# robo_mantis.net
KiCad netlist of a schematic drawn in EAGLE
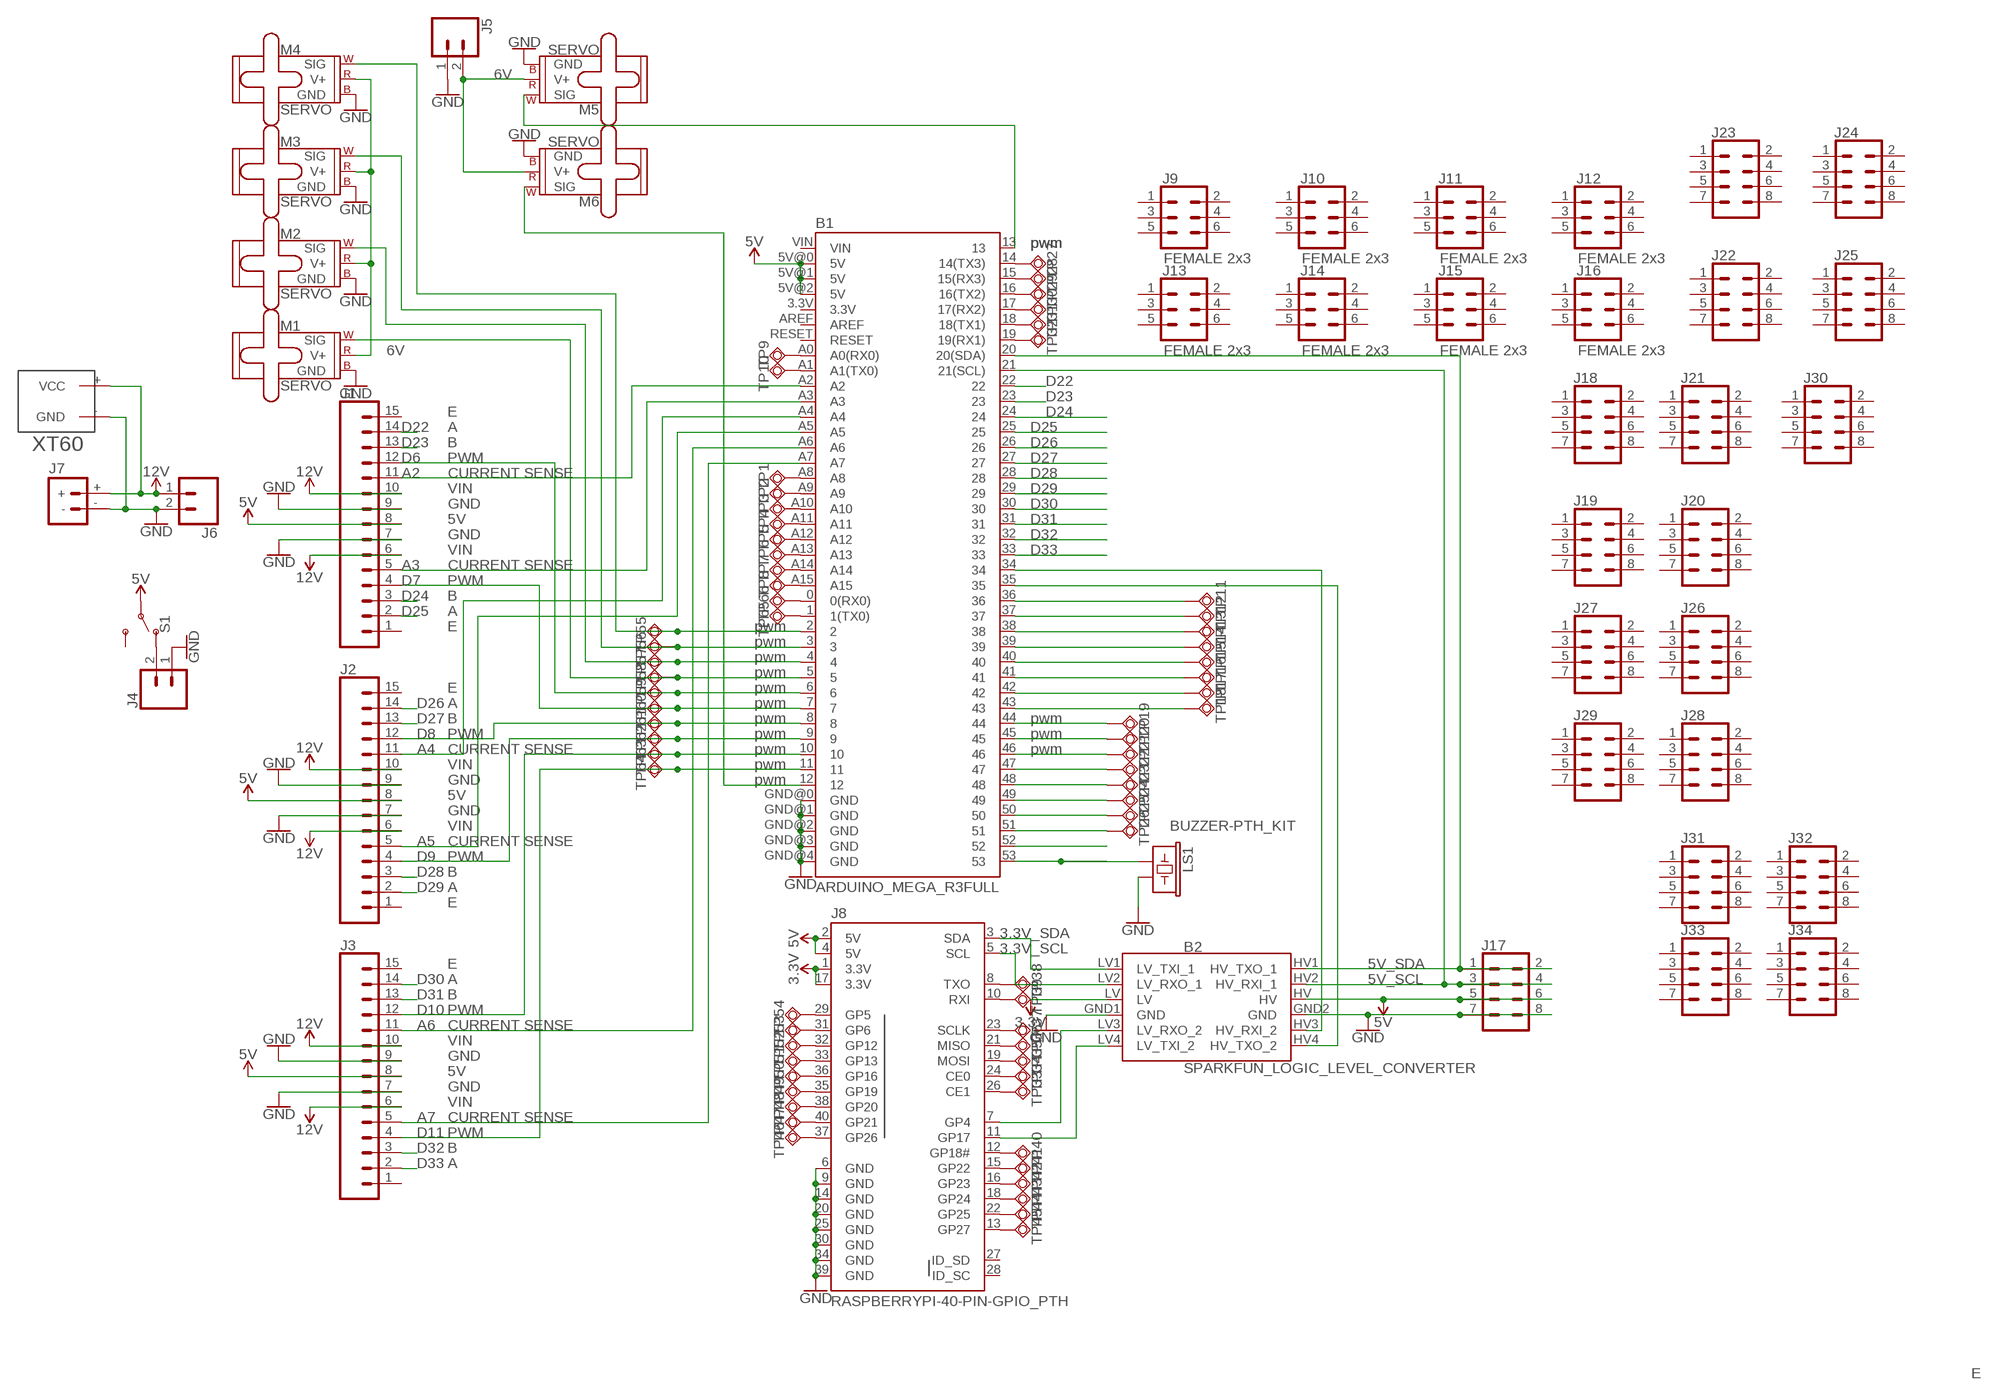
[diagram p0: schematic, sheet 1]

(export (version "E")
  (design (tool "Eeschema 10.0.6"))
  (components
    (comp (ref "B1")
      (value "ARDUINO_MEGA_R3FULL")
      (footprint "eagle-import:ARDUINO_MEGA")
      (libsource (lib "eagle-import") (part "ARDUINO_MEGA_R3FULL"))
    )
    (comp (ref "B2")
      (value "SPARKFUN_LOGIC_LEVEL_CONVERTER")
      (footprint "eagle-import:SPARKFUN_LOGIC_LEVEL_CONVERTER")
      (libsource (lib "eagle-import") (part "SPARKFUN_LOGIC_LEVEL_CONVERTER"))
    )
    (comp (ref "J1")
      (value "CONN_15LOCK_LONGPADS")
      (footprint "eagle-import:1X15_LOCK_LONGPADS")
      (libsource (lib "eagle-import") (part "CONN_15LOCK_LONGPADS"))
    )
    (comp (ref "J2")
      (value "CONN_15LOCK_LONGPADS")
      (footprint "eagle-import:1X15_LOCK_LONGPADS")
      (libsource (lib "eagle-import") (part "CONN_15LOCK_LONGPADS"))
    )
    (comp (ref "J3")
      (value "CONN_15LOCK_LONGPADS")
      (footprint "eagle-import:1X15_LOCK_LONGPADS")
      (libsource (lib "eagle-import") (part "CONN_15LOCK_LONGPADS"))
    )
    (comp (ref "J4")
      (value "CONN_02")
      (footprint "eagle-import:1X02")
      (libsource (lib "eagle-import") (part "CONN_02"))
    )
    (comp (ref "J5")
      (value "CONN_02")
      (footprint "eagle-import:1X02")
      (libsource (lib "eagle-import") (part "CONN_02"))
    )
    (comp (ref "J6")
      (value "CONN_02")
      (footprint "eagle-import:1X02")
      (libsource (lib "eagle-import") (part "CONN_02"))
    )
    (comp (ref "J7")
      (value "BATTERY_CONN_DEANS")
      (footprint "eagle-import:DEANS")
      (libsource (lib "eagle-import") (part "BATTERY_CONN_DEANS"))
    )
    (comp (ref "J8")
      (value "RASPBERRYPI-40-PIN-GPIO_PTH")
      (footprint "eagle-import:2X20_SHROUDED")
      (libsource (lib "eagle-import") (part "RASPBERRYPI-40-PIN-GPIO_PTH"))
    )
    (comp (ref "J9")
      (value "FEMALE 2x3")
      (footprint "eagle-import:2X3")
      (libsource (lib "eagle-import") (part "CONN_03X2FEMALE"))
    )
    (comp (ref "J10")
      (value "FEMALE 2x3")
      (footprint "eagle-import:2X3")
      (libsource (lib "eagle-import") (part "CONN_03X2FEMALE"))
    )
    (comp (ref "J11")
      (value "FEMALE 2x3")
      (footprint "eagle-import:2X3")
      (libsource (lib "eagle-import") (part "CONN_03X2FEMALE"))
    )
    (comp (ref "J12")
      (value "FEMALE 2x3")
      (footprint "eagle-import:2X3")
      (libsource (lib "eagle-import") (part "CONN_03X2FEMALE"))
    )
    (comp (ref "J13")
      (value "FEMALE 2x3")
      (footprint "eagle-import:2X3")
      (libsource (lib "eagle-import") (part "CONN_03X2FEMALE"))
    )
    (comp (ref "J14")
      (value "FEMALE 2x3")
      (footprint "eagle-import:2X3")
      (libsource (lib "eagle-import") (part "CONN_03X2FEMALE"))
    )
    (comp (ref "J15")
      (value "FEMALE 2x3")
      (footprint "eagle-import:2X3")
      (libsource (lib "eagle-import") (part "CONN_03X2FEMALE"))
    )
    (comp (ref "J16")
      (value "FEMALE 2x3")
      (footprint "eagle-import:2X3")
      (libsource (lib "eagle-import") (part "CONN_03X2FEMALE"))
    )
    (comp (ref "J17")
      (value "CONN_04X2")
      (footprint "eagle-import:2X4")
      (libsource (lib "eagle-import") (part "CONN_04X2"))
    )
    (comp (ref "J18")
      (value "CONN_04X2")
      (footprint "eagle-import:2X4")
      (libsource (lib "eagle-import") (part "CONN_04X2"))
    )
    (comp (ref "J19")
      (value "CONN_04X2")
      (footprint "eagle-import:2X4")
      (libsource (lib "eagle-import") (part "CONN_04X2"))
    )
    (comp (ref "J20")
      (value "CONN_04X2")
      (footprint "eagle-import:2X4")
      (libsource (lib "eagle-import") (part "CONN_04X2"))
    )
    (comp (ref "J21")
      (value "CONN_04X2")
      (footprint "eagle-import:2X4")
      (libsource (lib "eagle-import") (part "CONN_04X2"))
    )
    (comp (ref "J22")
      (value "CONN_04X2")
      (footprint "eagle-import:2X4")
      (libsource (lib "eagle-import") (part "CONN_04X2"))
    )
    (comp (ref "J23")
      (value "CONN_04X2")
      (footprint "eagle-import:2X4")
      (libsource (lib "eagle-import") (part "CONN_04X2"))
    )
    (comp (ref "J24")
      (value "CONN_04X2")
      (footprint "eagle-import:2X4")
      (libsource (lib "eagle-import") (part "CONN_04X2"))
    )
    (comp (ref "J25")
      (value "CONN_04X2")
      (footprint "eagle-import:2X4")
      (libsource (lib "eagle-import") (part "CONN_04X2"))
    )
    (comp (ref "J26")
      (value "CONN_04X2")
      (footprint "eagle-import:2X4")
      (libsource (lib "eagle-import") (part "CONN_04X2"))
    )
    (comp (ref "J27")
      (value "CONN_04X2")
      (footprint "eagle-import:2X4")
      (libsource (lib "eagle-import") (part "CONN_04X2"))
    )
    (comp (ref "J28")
      (value "CONN_04X2")
      (footprint "eagle-import:2X4")
      (libsource (lib "eagle-import") (part "CONN_04X2"))
    )
    (comp (ref "J29")
      (value "CONN_04X2")
      (footprint "eagle-import:2X4")
      (libsource (lib "eagle-import") (part "CONN_04X2"))
    )
    (comp (ref "J30")
      (value "CONN_04X2")
      (footprint "eagle-import:2X4")
      (libsource (lib "eagle-import") (part "CONN_04X2"))
    )
    (comp (ref "J31")
      (value "CONN_04X2")
      (footprint "eagle-import:2X4")
      (libsource (lib "eagle-import") (part "CONN_04X2"))
    )
    (comp (ref "J32")
      (value "CONN_04X2")
      (footprint "eagle-import:2X4")
      (libsource (lib "eagle-import") (part "CONN_04X2"))
    )
    (comp (ref "J33")
      (value "CONN_04X2")
      (footprint "eagle-import:2X4")
      (libsource (lib "eagle-import") (part "CONN_04X2"))
    )
    (comp (ref "J34")
      (value "CONN_04X2")
      (footprint "eagle-import:2X4")
      (libsource (lib "eagle-import") (part "CONN_04X2"))
    )
    (comp (ref "LS1")
      (value "BUZZER-PTH_KIT")
      (footprint "eagle-import:BUZZER-12MM-KIT")
      (libsource (lib "eagle-import") (part "BUZZER-PTH_KIT"))
    )
    (comp (ref "M1")
      (value "SERVO")
      (footprint "eagle-import:1X03")
      (libsource (lib "eagle-import") (part "SERVO"))
    )
    (comp (ref "M2")
      (value "SERVO")
      (footprint "eagle-import:1X03")
      (libsource (lib "eagle-import") (part "SERVO"))
    )
    (comp (ref "M3")
      (value "SERVO")
      (footprint "eagle-import:1X03")
      (libsource (lib "eagle-import") (part "SERVO"))
    )
    (comp (ref "M4")
      (value "SERVO")
      (footprint "eagle-import:1X03")
      (libsource (lib "eagle-import") (part "SERVO"))
    )
    (comp (ref "M5")
      (value "SERVO")
      (footprint "eagle-import:1X03")
      (libsource (lib "eagle-import") (part "SERVO"))
    )
    (comp (ref "M6")
      (value "SERVO")
      (footprint "eagle-import:1X03")
      (libsource (lib "eagle-import") (part "SERVO"))
    )
    (comp (ref "S1")
      (value "SWITCH-SPDT-PTH-11.6X4.0MM-LOCK")
      (footprint "eagle-import:SWITCH_SPDT_PTH_11.6X4.0MM_LOCK")
      (libsource (lib "eagle-import") (part "SWITCH-SPDT-PTH-11.6X4.0MM-LOCK"))
    )
    (comp (ref "TP1")
      (value "TESTPAD_TPSQB1,27")
      (footprint "eagle-import:TESTPAD_B1,27")
      (libsource (lib "eagle-import") (part "TESTPAD_TPSQB1,27"))
    )
    (comp (ref "TP2")
      (value "TESTPAD_TPSQB1,27")
      (footprint "eagle-import:TESTPAD_B1,27")
      (libsource (lib "eagle-import") (part "TESTPAD_TPSQB1,27"))
    )
    (comp (ref "TP3")
      (value "TESTPAD_TPSQB1,27")
      (footprint "eagle-import:TESTPAD_B1,27")
      (libsource (lib "eagle-import") (part "TESTPAD_TPSQB1,27"))
    )
    (comp (ref "TP4")
      (value "TESTPAD_TPSQB1,27")
      (footprint "eagle-import:TESTPAD_B1,27")
      (libsource (lib "eagle-import") (part "TESTPAD_TPSQB1,27"))
    )
    (comp (ref "TP5")
      (value "TESTPAD_TPSQB1,27")
      (footprint "eagle-import:TESTPAD_B1,27")
      (libsource (lib "eagle-import") (part "TESTPAD_TPSQB1,27"))
    )
    (comp (ref "TP6")
      (value "TESTPAD_TPSQB1,27")
      (footprint "eagle-import:TESTPAD_B1,27")
      (libsource (lib "eagle-import") (part "TESTPAD_TPSQB1,27"))
    )
    (comp (ref "TP7")
      (value "TESTPAD_TPSQB1,27")
      (footprint "eagle-import:TESTPAD_B1,27")
      (libsource (lib "eagle-import") (part "TESTPAD_TPSQB1,27"))
    )
    (comp (ref "TP8")
      (value "TESTPAD_TPSQB1,27")
      (footprint "eagle-import:TESTPAD_B1,27")
      (libsource (lib "eagle-import") (part "TESTPAD_TPSQB1,27"))
    )
    (comp (ref "TP9")
      (value "TESTPAD_TPSQB1,27")
      (footprint "eagle-import:TESTPAD_B1,27")
      (libsource (lib "eagle-import") (part "TESTPAD_TPSQB1,27"))
    )
    (comp (ref "TP10")
      (value "TESTPAD_TPSQB1,27")
      (footprint "eagle-import:TESTPAD_B1,27")
      (libsource (lib "eagle-import") (part "TESTPAD_TPSQB1,27"))
    )
    (comp (ref "TP11")
      (value "TESTPAD_TPSQB1,27")
      (footprint "eagle-import:TESTPAD_B1,27")
      (libsource (lib "eagle-import") (part "TESTPAD_TPSQB1,27"))
    )
    (comp (ref "TP12")
      (value "TESTPAD_TPSQB1,27")
      (footprint "eagle-import:TESTPAD_B1,27")
      (libsource (lib "eagle-import") (part "TESTPAD_TPSQB1,27"))
    )
    (comp (ref "TP13")
      (value "TESTPAD_TPSQB1,27")
      (footprint "eagle-import:TESTPAD_B1,27")
      (libsource (lib "eagle-import") (part "TESTPAD_TPSQB1,27"))
    )
    (comp (ref "TP14")
      (value "TESTPAD_TPSQB1,27")
      (footprint "eagle-import:TESTPAD_B1,27")
      (libsource (lib "eagle-import") (part "TESTPAD_TPSQB1,27"))
    )
    (comp (ref "TP15")
      (value "TESTPAD_TPSQB1,27")
      (footprint "eagle-import:TESTPAD_B1,27")
      (libsource (lib "eagle-import") (part "TESTPAD_TPSQB1,27"))
    )
    (comp (ref "TP16")
      (value "TESTPAD_TPSQB1,27")
      (footprint "eagle-import:TESTPAD_B1,27")
      (libsource (lib "eagle-import") (part "TESTPAD_TPSQB1,27"))
    )
    (comp (ref "TP17")
      (value "TESTPAD_TPSQB1,27")
      (footprint "eagle-import:TESTPAD_B1,27")
      (libsource (lib "eagle-import") (part "TESTPAD_TPSQB1,27"))
    )
    (comp (ref "TP18")
      (value "TESTPAD_TPSQB1,27")
      (footprint "eagle-import:TESTPAD_B1,27")
      (libsource (lib "eagle-import") (part "TESTPAD_TPSQB1,27"))
    )
    (comp (ref "TP19")
      (value "TESTPAD_TPSQB1,27")
      (footprint "eagle-import:TESTPAD_B1,27")
      (libsource (lib "eagle-import") (part "TESTPAD_TPSQB1,27"))
    )
    (comp (ref "TP20")
      (value "TESTPAD_TPSQB1,27")
      (footprint "eagle-import:TESTPAD_B1,27")
      (libsource (lib "eagle-import") (part "TESTPAD_TPSQB1,27"))
    )
    (comp (ref "TP21")
      (value "TESTPAD_TPSQB1,27")
      (footprint "eagle-import:TESTPAD_B1,27")
      (libsource (lib "eagle-import") (part "TESTPAD_TPSQB1,27"))
    )
    (comp (ref "TP22")
      (value "TESTPAD_TPSQB1,27")
      (footprint "eagle-import:TESTPAD_B1,27")
      (libsource (lib "eagle-import") (part "TESTPAD_TPSQB1,27"))
    )
    (comp (ref "TP23")
      (value "TESTPAD_TPSQB1,27")
      (footprint "eagle-import:TESTPAD_B1,27")
      (libsource (lib "eagle-import") (part "TESTPAD_TPSQB1,27"))
    )
    (comp (ref "TP24")
      (value "TESTPAD_TPSQB1,27")
      (footprint "eagle-import:TESTPAD_B1,27")
      (libsource (lib "eagle-import") (part "TESTPAD_TPSQB1,27"))
    )
    (comp (ref "TP25")
      (value "TESTPAD_TPSQB1,27")
      (footprint "eagle-import:TESTPAD_B1,27")
      (libsource (lib "eagle-import") (part "TESTPAD_TPSQB1,27"))
    )
    (comp (ref "TP26")
      (value "TESTPAD_TPSQB1,27")
      (footprint "eagle-import:TESTPAD_B1,27")
      (libsource (lib "eagle-import") (part "TESTPAD_TPSQB1,27"))
    )
    (comp (ref "TP27")
      (value "TESTPAD_TPSQB1,27")
      (footprint "eagle-import:TESTPAD_B1,27")
      (libsource (lib "eagle-import") (part "TESTPAD_TPSQB1,27"))
    )
    (comp (ref "TP28")
      (value "TESTPAD_TPSQB1,27")
      (footprint "eagle-import:TESTPAD_B1,27")
      (libsource (lib "eagle-import") (part "TESTPAD_TPSQB1,27"))
    )
    (comp (ref "TP29")
      (value "TESTPAD_TPSQB1,27")
      (footprint "eagle-import:TESTPAD_B1,27")
      (libsource (lib "eagle-import") (part "TESTPAD_TPSQB1,27"))
    )
    (comp (ref "TP30")
      (value "TESTPAD_TPSQB1,27")
      (footprint "eagle-import:TESTPAD_B1,27")
      (libsource (lib "eagle-import") (part "TESTPAD_TPSQB1,27"))
    )
    (comp (ref "TP31")
      (value "TESTPAD_TPSQB1,27")
      (footprint "eagle-import:TESTPAD_B1,27")
      (libsource (lib "eagle-import") (part "TESTPAD_TPSQB1,27"))
    )
    (comp (ref "TP32")
      (value "TESTPAD_TPSQB1,27")
      (footprint "eagle-import:TESTPAD_B1,27")
      (libsource (lib "eagle-import") (part "TESTPAD_TPSQB1,27"))
    )
    (comp (ref "TP33")
      (value "TESTPAD_TPSQB1,27")
      (footprint "eagle-import:TESTPAD_B1,27")
      (libsource (lib "eagle-import") (part "TESTPAD_TPSQB1,27"))
    )
    (comp (ref "TP34")
      (value "TESTPAD_TPSQB1,27")
      (footprint "eagle-import:TESTPAD_B1,27")
      (libsource (lib "eagle-import") (part "TESTPAD_TPSQB1,27"))
    )
    (comp (ref "TP35")
      (value "TESTPAD_TPSQB1,27")
      (footprint "eagle-import:TESTPAD_B1,27")
      (libsource (lib "eagle-import") (part "TESTPAD_TPSQB1,27"))
    )
    (comp (ref "TP36")
      (value "TESTPAD_TPSQB1,27")
      (footprint "eagle-import:TESTPAD_B1,27")
      (libsource (lib "eagle-import") (part "TESTPAD_TPSQB1,27"))
    )
    (comp (ref "TP37")
      (value "TESTPAD_TPSQB1,27")
      (footprint "eagle-import:TESTPAD_B1,27")
      (libsource (lib "eagle-import") (part "TESTPAD_TPSQB1,27"))
    )
    (comp (ref "TP38")
      (value "TESTPAD_TPSQB1,27")
      (footprint "eagle-import:TESTPAD_B1,27")
      (libsource (lib "eagle-import") (part "TESTPAD_TPSQB1,27"))
    )
    (comp (ref "TP39")
      (value "TESTPAD_TPSQB1,27")
      (footprint "eagle-import:TESTPAD_B1,27")
      (libsource (lib "eagle-import") (part "TESTPAD_TPSQB1,27"))
    )
    (comp (ref "TP40")
      (value "TESTPAD_TPSQB1,27")
      (footprint "eagle-import:TESTPAD_B1,27")
      (libsource (lib "eagle-import") (part "TESTPAD_TPSQB1,27"))
    )
    (comp (ref "TP41")
      (value "TESTPAD_TPSQB1,27")
      (footprint "eagle-import:TESTPAD_B1,27")
      (libsource (lib "eagle-import") (part "TESTPAD_TPSQB1,27"))
    )
    (comp (ref "TP42")
      (value "TESTPAD_TPSQB1,27")
      (footprint "eagle-import:TESTPAD_B1,27")
      (libsource (lib "eagle-import") (part "TESTPAD_TPSQB1,27"))
    )
    (comp (ref "TP43")
      (value "TESTPAD_TPSQB1,27")
      (footprint "eagle-import:TESTPAD_B1,27")
      (libsource (lib "eagle-import") (part "TESTPAD_TPSQB1,27"))
    )
    (comp (ref "TP44")
      (value "TESTPAD_TPSQB1,27")
      (footprint "eagle-import:TESTPAD_B1,27")
      (libsource (lib "eagle-import") (part "TESTPAD_TPSQB1,27"))
    )
    (comp (ref "TP45")
      (value "TESTPAD_TPSQB1,27")
      (footprint "eagle-import:TESTPAD_B1,27")
      (libsource (lib "eagle-import") (part "TESTPAD_TPSQB1,27"))
    )
    (comp (ref "TP46")
      (value "TESTPAD_TPSQB1,27")
      (footprint "eagle-import:TESTPAD_B1,27")
      (libsource (lib "eagle-import") (part "TESTPAD_TPSQB1,27"))
    )
    (comp (ref "TP47")
      (value "TESTPAD_TPSQB1,27")
      (footprint "eagle-import:TESTPAD_B1,27")
      (libsource (lib "eagle-import") (part "TESTPAD_TPSQB1,27"))
    )
    (comp (ref "TP48")
      (value "TESTPAD_TPSQB1,27")
      (footprint "eagle-import:TESTPAD_B1,27")
      (libsource (lib "eagle-import") (part "TESTPAD_TPSQB1,27"))
    )
    (comp (ref "TP49")
      (value "TESTPAD_TPSQB1,27")
      (footprint "eagle-import:TESTPAD_B1,27")
      (libsource (lib "eagle-import") (part "TESTPAD_TPSQB1,27"))
    )
    (comp (ref "TP50")
      (value "TESTPAD_TPSQB1,27")
      (footprint "eagle-import:TESTPAD_B1,27")
      (libsource (lib "eagle-import") (part "TESTPAD_TPSQB1,27"))
    )
    (comp (ref "TP51")
      (value "TESTPAD_TPSQB1,27")
      (footprint "eagle-import:TESTPAD_B1,27")
      (libsource (lib "eagle-import") (part "TESTPAD_TPSQB1,27"))
    )
    (comp (ref "TP52")
      (value "TESTPAD_TPSQB1,27")
      (footprint "eagle-import:TESTPAD_B1,27")
      (libsource (lib "eagle-import") (part "TESTPAD_TPSQB1,27"))
    )
    (comp (ref "TP53")
      (value "TESTPAD_TPSQB1,27")
      (footprint "eagle-import:TESTPAD_B1,27")
      (libsource (lib "eagle-import") (part "TESTPAD_TPSQB1,27"))
    )
    (comp (ref "TP54")
      (value "TESTPAD_TPSQB1,27")
      (footprint "eagle-import:TESTPAD_B1,27")
      (libsource (lib "eagle-import") (part "TESTPAD_TPSQB1,27"))
    )
    (comp (ref "TP55")
      (value "TESTPAD_TPSQB1,27")
      (footprint "eagle-import:TESTPAD_B1,27")
      (libsource (lib "eagle-import") (part "TESTPAD_TPSQB1,27"))
    )
    (comp (ref "TP56")
      (value "TESTPAD_TPSQB1,27")
      (footprint "eagle-import:TESTPAD_B1,27")
      (libsource (lib "eagle-import") (part "TESTPAD_TPSQB1,27"))
    )
    (comp (ref "TP57")
      (value "TESTPAD_TPSQB1,27")
      (footprint "eagle-import:TESTPAD_B1,27")
      (libsource (lib "eagle-import") (part "TESTPAD_TPSQB1,27"))
    )
    (comp (ref "TP58")
      (value "TESTPAD_TPSQB1,27")
      (footprint "eagle-import:TESTPAD_B1,27")
      (libsource (lib "eagle-import") (part "TESTPAD_TPSQB1,27"))
    )
    (comp (ref "TP59")
      (value "TESTPAD_TPSQB1,27")
      (footprint "eagle-import:TESTPAD_B1,27")
      (libsource (lib "eagle-import") (part "TESTPAD_TPSQB1,27"))
    )
    (comp (ref "TP60")
      (value "TESTPAD_TPSQB1,27")
      (footprint "eagle-import:TESTPAD_B1,27")
      (libsource (lib "eagle-import") (part "TESTPAD_TPSQB1,27"))
    )
    (comp (ref "TP61")
      (value "TESTPAD_TPSQB1,27")
      (footprint "eagle-import:TESTPAD_B1,27")
      (libsource (lib "eagle-import") (part "TESTPAD_TPSQB1,27"))
    )
    (comp (ref "TP62")
      (value "TESTPAD_TPSQB1,27")
      (footprint "eagle-import:TESTPAD_B1,27")
      (libsource (lib "eagle-import") (part "TESTPAD_TPSQB1,27"))
    )
    (comp (ref "TP63")
      (value "TESTPAD_TPSQB1,27")
      (footprint "eagle-import:TESTPAD_B1,27")
      (libsource (lib "eagle-import") (part "TESTPAD_TPSQB1,27"))
    )
    (comp (ref "TP64")
      (value "TESTPAD_TPSQB1,27")
      (footprint "eagle-import:TESTPAD_B1,27")
      (libsource (lib "eagle-import") (part "TESTPAD_TPSQB1,27"))
    )
    (comp (ref "TP65")
      (value "TESTPAD_TPSQB1,27")
      (footprint "eagle-import:TESTPAD_B1,27")
      (libsource (lib "eagle-import") (part "TESTPAD_TPSQB1,27"))
    )
    (comp (ref "TP66")
      (value "TESTPAD_TPSQB1,27")
      (footprint "eagle-import:TESTPAD_B1,27")
      (libsource (lib "eagle-import") (part "TESTPAD_TPSQB1,27"))
    )
    (comp (ref "U$1")
      (value "XT60")
      (footprint "eagle-import:XT60")
      (libsource (lib "eagle-import") (part "XT60"))
    )
  )
  (nets
    (net (code "1") (name "/3.3V_SCL") (class "Default")
      (node (ref "B2") (pin "LV2") (pinfunction "LV_RXO_1_LV2") (pintype "bidirectional"))
      (node (ref "J8") (pin "5") (pinfunction "SCL_5") (pintype "bidirectional"))
    )
    (net (code "2") (name "/3.3V_SDA") (class "Default")
      (node (ref "B2") (pin "LV1") (pinfunction "LV_TXI_1_LV1") (pintype "bidirectional"))
      (node (ref "J8") (pin "3") (pinfunction "SDA_3") (pintype "bidirectional"))
    )
    (net (code "3") (name "/5V_SCL") (class "Default")
      (node (ref "B1") (pin "21") (pinfunction "21(SCL)_21") (pintype "bidirectional"))
      (node (ref "B2") (pin "HV2") (pinfunction "HV_RXI_1_HV2") (pintype "bidirectional"))
      (node (ref "J17") (pin "3") (pinfunction "3_3") (pintype "passive"))
      (node (ref "J17") (pin "4") (pinfunction "4_4") (pintype "passive"))
    )
    (net (code "4") (name "/5V_SDA") (class "Default")
      (node (ref "B1") (pin "20") (pinfunction "20(SDA)_20") (pintype "bidirectional"))
      (node (ref "B2") (pin "HV1") (pinfunction "HV_TXO_1_HV1") (pintype "bidirectional"))
      (node (ref "J17") (pin "1") (pinfunction "1_1") (pintype "passive"))
      (node (ref "J17") (pin "2") (pinfunction "2_2") (pintype "passive"))
    )
    (net (code "5") (name "/6V") (class "Default")
      (node (ref "J5") (pin "2") (pinfunction "2_2") (pintype "passive"))
      (node (ref "M1") (pin "2") (pinfunction "V+_2") (pintype "bidirectional"))
      (node (ref "M2") (pin "2") (pinfunction "V+_2") (pintype "bidirectional"))
      (node (ref "M3") (pin "2") (pinfunction "V+_2") (pintype "bidirectional"))
      (node (ref "M4") (pin "2") (pinfunction "V+_2") (pintype "bidirectional"))
      (node (ref "M5") (pin "2") (pinfunction "V+_2") (pintype "bidirectional"))
      (node (ref "M6") (pin "2") (pinfunction "V+_2") (pintype "bidirectional"))
    )
    (net (code "6") (name "/A2") (class "Default")
      (node (ref "B1") (pin "A2") (pinfunction "A2_A2") (pintype "bidirectional"))
      (node (ref "J1") (pin "11") (pinfunction "11_11") (pintype "passive"))
    )
    (net (code "7") (name "/A3") (class "Default")
      (node (ref "B1") (pin "A3") (pinfunction "A3_A3") (pintype "bidirectional"))
      (node (ref "J1") (pin "5") (pinfunction "5_5") (pintype "passive"))
    )
    (net (code "8") (name "/A4") (class "Default")
      (node (ref "B1") (pin "A4") (pinfunction "A4_A4") (pintype "bidirectional"))
      (node (ref "J2") (pin "11") (pinfunction "11_11") (pintype "passive"))
    )
    (net (code "9") (name "/A5") (class "Default")
      (node (ref "B1") (pin "A5") (pinfunction "A5_A5") (pintype "bidirectional"))
      (node (ref "J2") (pin "5") (pinfunction "5_5") (pintype "passive"))
    )
    (net (code "10") (name "/A6") (class "Default")
      (node (ref "B1") (pin "A6") (pinfunction "A6_A6") (pintype "bidirectional"))
      (node (ref "J3") (pin "11") (pinfunction "11_11") (pintype "passive"))
    )
    (net (code "11") (name "/A7") (class "Default")
      (node (ref "B1") (pin "A7") (pinfunction "A7_A7") (pintype "bidirectional"))
      (node (ref "J3") (pin "5") (pinfunction "5_5") (pintype "passive"))
    )
    (net (code "12") (name "/D6") (class "Default")
      (node (ref "B1") (pin "6") (pinfunction "6_6") (pintype "bidirectional"))
      (node (ref "J1") (pin "12") (pinfunction "12_12") (pintype "passive"))
      (node (ref "TP59") (pin "TP") (pinfunction "TP_TP") (pintype "input"))
    )
    (net (code "13") (name "/D7") (class "Default")
      (node (ref "B1") (pin "7") (pinfunction "7_7") (pintype "bidirectional"))
      (node (ref "J1") (pin "4") (pinfunction "4_4") (pintype "passive"))
      (node (ref "TP60") (pin "TP") (pinfunction "TP_TP") (pintype "input"))
    )
    (net (code "14") (name "/D8") (class "Default")
      (node (ref "B1") (pin "8") (pinfunction "8_8") (pintype "bidirectional"))
      (node (ref "J2") (pin "12") (pinfunction "12_12") (pintype "passive"))
      (node (ref "TP61") (pin "TP") (pinfunction "TP_TP") (pintype "input"))
    )
    (net (code "15") (name "/D9") (class "Default")
      (node (ref "B1") (pin "9") (pinfunction "9_9") (pintype "bidirectional"))
      (node (ref "J2") (pin "4") (pinfunction "4_4") (pintype "passive"))
      (node (ref "TP62") (pin "TP") (pinfunction "TP_TP") (pintype "input"))
    )
    (net (code "16") (name "/D10") (class "Default")
      (node (ref "B1") (pin "10") (pinfunction "10_10") (pintype "bidirectional"))
      (node (ref "J3") (pin "12") (pinfunction "12_12") (pintype "passive"))
      (node (ref "TP63") (pin "TP") (pinfunction "TP_TP") (pintype "input"))
    )
    (net (code "17") (name "/D11") (class "Default")
      (node (ref "B1") (pin "11") (pinfunction "11_11") (pintype "bidirectional"))
      (node (ref "J3") (pin "4") (pinfunction "4_4") (pintype "passive"))
      (node (ref "TP64") (pin "TP") (pinfunction "TP_TP") (pintype "input"))
    )
    (net (code "18") (name "/D22") (class "Default")
      (node (ref "B1") (pin "22") (pinfunction "22_22") (pintype "bidirectional"))
      (node (ref "J1") (pin "14") (pinfunction "14_14") (pintype "passive"))
    )
    (net (code "19") (name "/D23") (class "Default")
      (node (ref "B1") (pin "23") (pinfunction "23_23") (pintype "bidirectional"))
      (node (ref "J1") (pin "13") (pinfunction "13_13") (pintype "passive"))
    )
    (net (code "20") (name "/D24") (class "Default")
      (node (ref "B1") (pin "24") (pinfunction "24_24") (pintype "bidirectional"))
      (node (ref "J1") (pin "3") (pinfunction "3_3") (pintype "passive"))
    )
    (net (code "21") (name "/D25") (class "Default")
      (node (ref "B1") (pin "25") (pinfunction "25_25") (pintype "bidirectional"))
      (node (ref "J1") (pin "2") (pinfunction "2_2") (pintype "passive"))
    )
    (net (code "22") (name "/D26") (class "Default")
      (node (ref "B1") (pin "26") (pinfunction "26_26") (pintype "bidirectional"))
      (node (ref "J2") (pin "14") (pinfunction "14_14") (pintype "passive"))
    )
    (net (code "23") (name "/D27") (class "Default")
      (node (ref "B1") (pin "27") (pinfunction "27_27") (pintype "bidirectional"))
      (node (ref "J2") (pin "13") (pinfunction "13_13") (pintype "passive"))
    )
    (net (code "24") (name "/D28") (class "Default")
      (node (ref "B1") (pin "28") (pinfunction "28_28") (pintype "bidirectional"))
      (node (ref "J2") (pin "3") (pinfunction "3_3") (pintype "passive"))
    )
    (net (code "25") (name "/D29") (class "Default")
      (node (ref "B1") (pin "29") (pinfunction "29_29") (pintype "bidirectional"))
      (node (ref "J2") (pin "2") (pinfunction "2_2") (pintype "passive"))
    )
    (net (code "26") (name "/D30") (class "Default")
      (node (ref "B1") (pin "30") (pinfunction "30_30") (pintype "bidirectional"))
      (node (ref "J3") (pin "14") (pinfunction "14_14") (pintype "passive"))
    )
    (net (code "27") (name "/D31") (class "Default")
      (node (ref "B1") (pin "31") (pinfunction "31_31") (pintype "bidirectional"))
      (node (ref "J3") (pin "13") (pinfunction "13_13") (pintype "passive"))
    )
    (net (code "28") (name "/D32") (class "Default")
      (node (ref "B1") (pin "32") (pinfunction "32_32") (pintype "bidirectional"))
      (node (ref "J3") (pin "3") (pinfunction "3_3") (pintype "passive"))
    )
    (net (code "29") (name "/D33") (class "Default")
      (node (ref "B1") (pin "33") (pinfunction "33_33") (pintype "bidirectional"))
      (node (ref "J3") (pin "2") (pinfunction "2_2") (pintype "passive"))
    )
    (net (code "30") (name "3.3V") (class "Default")
      (node (ref "B2") (pin "LV") (pinfunction "LV_LV") (pintype "power_in"))
      (node (ref "J8") (pin "1") (pinfunction "3.3V_1") (pintype "power_in"))
      (node (ref "J8") (pin "17") (pinfunction "3.3V_17") (pintype "power_in"))
    )
    (net (code "31") (name "5V") (class "Default")
      (node (ref "B1") (pin "5V@0") (pinfunction "5V_5V@0") (pintype "bidirectional"))
      (node (ref "B1") (pin "5V@1") (pinfunction "5V_5V@1") (pintype "bidirectional"))
      (node (ref "B1") (pin "5V@2") (pinfunction "5V_5V@2") (pintype "bidirectional"))
      (node (ref "B2") (pin "HV") (pinfunction "HV_HV") (pintype "power_in"))
      (node (ref "J1") (pin "8") (pinfunction "8_8") (pintype "passive"))
      (node (ref "J17") (pin "5") (pinfunction "5_5") (pintype "passive"))
      (node (ref "J17") (pin "6") (pinfunction "6_6") (pintype "passive"))
      (node (ref "J2") (pin "8") (pinfunction "8_8") (pintype "passive"))
      (node (ref "J3") (pin "8") (pinfunction "8_8") (pintype "passive"))
      (node (ref "J8") (pin "2") (pinfunction "5V_2") (pintype "power_in"))
      (node (ref "J8") (pin "4") (pinfunction "5V_4") (pintype "power_in"))
      (node (ref "S1") (pin "2") (pinfunction "P_2") (pintype "passive"))
    )
    (net (code "32") (name "12V") (class "Default")
      (node (ref "J1") (pin "10") (pinfunction "10_10") (pintype "passive"))
      (node (ref "J1") (pin "6") (pinfunction "6_6") (pintype "passive"))
      (node (ref "J2") (pin "10") (pinfunction "10_10") (pintype "passive"))
      (node (ref "J2") (pin "6") (pinfunction "6_6") (pintype "passive"))
      (node (ref "J3") (pin "10") (pinfunction "10_10") (pintype "passive"))
      (node (ref "J3") (pin "6") (pinfunction "6_6") (pintype "passive"))
      (node (ref "J6") (pin "1") (pinfunction "1_1") (pintype "passive"))
      (node (ref "J7") (pin "+") (pinfunction "+_+") (pintype "passive"))
      (node (ref "U$1") (pin "+") (pinfunction "VCC_+") (pintype "bidirectional"))
    )
    (net (code "33") (name "GND") (class "Default")
      (node (ref "B1") (pin "GND@0") (pinfunction "GND_GND@0") (pintype "bidirectional"))
      (node (ref "B1") (pin "GND@1") (pinfunction "GND_GND@1") (pintype "bidirectional"))
      (node (ref "B1") (pin "GND@2") (pinfunction "GND_GND@2") (pintype "bidirectional"))
      (node (ref "B1") (pin "GND@3") (pinfunction "GND_GND@3") (pintype "bidirectional"))
      (node (ref "B1") (pin "GND@4") (pinfunction "GND_GND@4") (pintype "bidirectional"))
      (node (ref "B2") (pin "GND1") (pinfunction "GND_GND1") (pintype "power_in"))
      (node (ref "B2") (pin "GND2") (pinfunction "GND_GND2") (pintype "power_in"))
      (node (ref "J1") (pin "7") (pinfunction "7_7") (pintype "passive"))
      (node (ref "J1") (pin "9") (pinfunction "9_9") (pintype "passive"))
      (node (ref "J17") (pin "7") (pinfunction "7_7") (pintype "passive"))
      (node (ref "J17") (pin "8") (pinfunction "8_8") (pintype "passive"))
      (node (ref "J2") (pin "7") (pinfunction "7_7") (pintype "passive"))
      (node (ref "J2") (pin "9") (pinfunction "9_9") (pintype "passive"))
      (node (ref "J3") (pin "7") (pinfunction "7_7") (pintype "passive"))
      (node (ref "J3") (pin "9") (pinfunction "9_9") (pintype "passive"))
      (node (ref "J4") (pin "1") (pinfunction "1_1") (pintype "passive"))
      (node (ref "J5") (pin "1") (pinfunction "1_1") (pintype "passive"))
      (node (ref "J6") (pin "2") (pinfunction "2_2") (pintype "passive"))
      (node (ref "J7") (pin "-") (pinfunction "-_-") (pintype "passive"))
      (node (ref "J8") (pin "14") (pinfunction "GND_14") (pintype "power_in"))
      (node (ref "J8") (pin "20") (pinfunction "GND_20") (pintype "power_in"))
      (node (ref "J8") (pin "25") (pinfunction "GND_25") (pintype "power_in"))
      (node (ref "J8") (pin "30") (pinfunction "GND_30") (pintype "power_in"))
      (node (ref "J8") (pin "34") (pinfunction "GND_34") (pintype "power_in"))
      (node (ref "J8") (pin "39") (pinfunction "GND_39") (pintype "power_in"))
      (node (ref "J8") (pin "6") (pinfunction "GND_6") (pintype "power_in"))
      (node (ref "J8") (pin "9") (pinfunction "GND_9") (pintype "power_in"))
      (node (ref "LS1") (pin "-") (pinfunction "2_-") (pintype "passive"))
      (node (ref "M1") (pin "3") (pinfunction "GND_3") (pintype "bidirectional"))
      (node (ref "M2") (pin "3") (pinfunction "GND_3") (pintype "bidirectional"))
      (node (ref "M3") (pin "3") (pinfunction "GND_3") (pintype "bidirectional"))
      (node (ref "M4") (pin "3") (pinfunction "GND_3") (pintype "bidirectional"))
      (node (ref "M5") (pin "3") (pinfunction "GND_3") (pintype "bidirectional"))
      (node (ref "M6") (pin "3") (pinfunction "GND_3") (pintype "bidirectional"))
      (node (ref "U$1") (pin "-") (pinfunction "GND_-") (pintype "bidirectional"))
    )
    (net (code "34") (name "Net-(B1-0(RX0))") (class "Default")
      (node (ref "B1") (pin "0") (pinfunction "0(RX0)_0") (pintype "bidirectional"))
      (node (ref "TP66") (pin "TP") (pinfunction "TP_TP") (pintype "input"))
    )
    (net (code "35") (name "Net-(B1-1(TX0))") (class "Default")
      (node (ref "B1") (pin "1") (pinfunction "1(TX0)_1") (pintype "bidirectional"))
      (node (ref "TP65") (pin "TP") (pinfunction "TP_TP") (pintype "input"))
    )
    (net (code "36") (name "Net-(B1-14(TX3))") (class "Default")
      (node (ref "B1") (pin "14") (pinfunction "14(TX3)_14") (pintype "bidirectional"))
      (node (ref "TP27") (pin "TP") (pinfunction "TP_TP") (pintype "input"))
    )
    (net (code "37") (name "Net-(B1-15(RX3))") (class "Default")
      (node (ref "B1") (pin "15") (pinfunction "15(RX3)_15") (pintype "bidirectional"))
      (node (ref "TP28") (pin "TP") (pinfunction "TP_TP") (pintype "input"))
    )
    (net (code "38") (name "Net-(B1-16(TX2))") (class "Default")
      (node (ref "B1") (pin "16") (pinfunction "16(TX2)_16") (pintype "bidirectional"))
      (node (ref "TP29") (pin "TP") (pinfunction "TP_TP") (pintype "input"))
    )
    (net (code "39") (name "Net-(B1-17(RX2))") (class "Default")
      (node (ref "B1") (pin "17") (pinfunction "17(RX2)_17") (pintype "bidirectional"))
      (node (ref "TP30") (pin "TP") (pinfunction "TP_TP") (pintype "input"))
    )
    (net (code "40") (name "Net-(B1-18(TX1))") (class "Default")
      (node (ref "B1") (pin "18") (pinfunction "18(TX1)_18") (pintype "bidirectional"))
      (node (ref "TP31") (pin "TP") (pinfunction "TP_TP") (pintype "input"))
    )
    (net (code "41") (name "Net-(B1-19(RX1))") (class "Default")
      (node (ref "B1") (pin "19") (pinfunction "19(RX1)_19") (pintype "bidirectional"))
      (node (ref "TP32") (pin "TP") (pinfunction "TP_TP") (pintype "input"))
    )
    (net (code "42") (name "Net-(B1-A0(RX0))") (class "Default")
      (node (ref "B1") (pin "A0") (pinfunction "A0(RX0)_A0") (pintype "bidirectional"))
      (node (ref "TP9") (pin "TP") (pinfunction "TP_TP") (pintype "input"))
    )
    (net (code "43") (name "Net-(B1-A1(TX0))") (class "Default")
      (node (ref "B1") (pin "A1") (pinfunction "A1(TX0)_A1") (pintype "bidirectional"))
      (node (ref "TP10") (pin "TP") (pinfunction "TP_TP") (pintype "input"))
    )
    (net (code "44") (name "Net-(B1-Pad36)") (class "Default")
      (node (ref "B1") (pin "36") (pinfunction "36_36") (pintype "bidirectional"))
      (node (ref "TP11") (pin "TP") (pinfunction "TP_TP") (pintype "input"))
    )
    (net (code "45") (name "Net-(B1-Pad37)") (class "Default")
      (node (ref "B1") (pin "37") (pinfunction "37_37") (pintype "bidirectional"))
      (node (ref "TP12") (pin "TP") (pinfunction "TP_TP") (pintype "input"))
    )
    (net (code "46") (name "Net-(B1-Pad38)") (class "Default")
      (node (ref "B1") (pin "38") (pinfunction "38_38") (pintype "bidirectional"))
      (node (ref "TP13") (pin "TP") (pinfunction "TP_TP") (pintype "input"))
    )
    (net (code "47") (name "Net-(B1-Pad39)") (class "Default")
      (node (ref "B1") (pin "39") (pinfunction "39_39") (pintype "bidirectional"))
      (node (ref "TP14") (pin "TP") (pinfunction "TP_TP") (pintype "input"))
    )
    (net (code "48") (name "Net-(B1-Pad40)") (class "Default")
      (node (ref "B1") (pin "40") (pinfunction "40_40") (pintype "bidirectional"))
      (node (ref "TP15") (pin "TP") (pinfunction "TP_TP") (pintype "input"))
    )
    (net (code "49") (name "Net-(B1-Pad41)") (class "Default")
      (node (ref "B1") (pin "41") (pinfunction "41_41") (pintype "bidirectional"))
      (node (ref "TP16") (pin "TP") (pinfunction "TP_TP") (pintype "input"))
    )
    (net (code "50") (name "Net-(B1-Pad42)") (class "Default")
      (node (ref "B1") (pin "42") (pinfunction "42_42") (pintype "bidirectional"))
      (node (ref "TP17") (pin "TP") (pinfunction "TP_TP") (pintype "input"))
    )
    (net (code "51") (name "Net-(B1-Pad43)") (class "Default")
      (node (ref "B1") (pin "43") (pinfunction "43_43") (pintype "bidirectional"))
      (node (ref "TP18") (pin "TP") (pinfunction "TP_TP") (pintype "input"))
    )
    (net (code "52") (name "Net-(B1-Pad44)") (class "Default")
      (node (ref "B1") (pin "44") (pinfunction "44_44") (pintype "bidirectional"))
      (node (ref "TP19") (pin "TP") (pinfunction "TP_TP") (pintype "input"))
    )
    (net (code "53") (name "Net-(B1-Pad45)") (class "Default")
      (node (ref "B1") (pin "45") (pinfunction "45_45") (pintype "bidirectional"))
      (node (ref "TP20") (pin "TP") (pinfunction "TP_TP") (pintype "input"))
    )
    (net (code "54") (name "Net-(B1-Pad46)") (class "Default")
      (node (ref "B1") (pin "46") (pinfunction "46_46") (pintype "bidirectional"))
      (node (ref "TP21") (pin "TP") (pinfunction "TP_TP") (pintype "input"))
    )
    (net (code "55") (name "Net-(B1-Pad47)") (class "Default")
      (node (ref "B1") (pin "47") (pinfunction "47_47") (pintype "bidirectional"))
      (node (ref "TP22") (pin "TP") (pinfunction "TP_TP") (pintype "input"))
    )
    (net (code "56") (name "Net-(B1-Pad48)") (class "Default")
      (node (ref "B1") (pin "48") (pinfunction "48_48") (pintype "bidirectional"))
      (node (ref "TP23") (pin "TP") (pinfunction "TP_TP") (pintype "input"))
    )
    (net (code "57") (name "Net-(B1-Pad49)") (class "Default")
      (node (ref "B1") (pin "49") (pinfunction "49_49") (pintype "bidirectional"))
      (node (ref "TP24") (pin "TP") (pinfunction "TP_TP") (pintype "input"))
    )
    (net (code "58") (name "Net-(B1-Pad50)") (class "Default")
      (node (ref "B1") (pin "50") (pinfunction "50_50") (pintype "bidirectional"))
      (node (ref "TP25") (pin "TP") (pinfunction "TP_TP") (pintype "input"))
    )
    (net (code "59") (name "Net-(B1-Pad51)") (class "Default")
      (node (ref "B1") (pin "51") (pinfunction "51_51") (pintype "bidirectional"))
      (node (ref "TP26") (pin "TP") (pinfunction "TP_TP") (pintype "input"))
    )
    (net (code "60") (name "Net-(B1-PadA8)") (class "Default")
      (node (ref "B1") (pin "A8") (pinfunction "A8_A8") (pintype "bidirectional"))
      (node (ref "TP1") (pin "TP") (pinfunction "TP_TP") (pintype "input"))
    )
    (net (code "61") (name "Net-(B1-PadA9)") (class "Default")
      (node (ref "B1") (pin "A9") (pinfunction "A9_A9") (pintype "bidirectional"))
      (node (ref "TP2") (pin "TP") (pinfunction "TP_TP") (pintype "input"))
    )
    (net (code "62") (name "Net-(B1-PadA10)") (class "Default")
      (node (ref "B1") (pin "A10") (pinfunction "A10_A10") (pintype "bidirectional"))
      (node (ref "TP3") (pin "TP") (pinfunction "TP_TP") (pintype "input"))
    )
    (net (code "63") (name "Net-(B1-PadA11)") (class "Default")
      (node (ref "B1") (pin "A11") (pinfunction "A11_A11") (pintype "bidirectional"))
      (node (ref "TP4") (pin "TP") (pinfunction "TP_TP") (pintype "input"))
    )
    (net (code "64") (name "Net-(B1-PadA12)") (class "Default")
      (node (ref "B1") (pin "A12") (pinfunction "A12_A12") (pintype "bidirectional"))
      (node (ref "TP5") (pin "TP") (pinfunction "TP_TP") (pintype "input"))
    )
    (net (code "65") (name "Net-(B1-PadA13)") (class "Default")
      (node (ref "B1") (pin "A13") (pinfunction "A13_A13") (pintype "bidirectional"))
      (node (ref "TP6") (pin "TP") (pinfunction "TP_TP") (pintype "input"))
    )
    (net (code "66") (name "Net-(B1-PadA14)") (class "Default")
      (node (ref "B1") (pin "A14") (pinfunction "A14_A14") (pintype "bidirectional"))
      (node (ref "TP7") (pin "TP") (pinfunction "TP_TP") (pintype "input"))
    )
    (net (code "67") (name "Net-(B1-PadA15)") (class "Default")
      (node (ref "B1") (pin "A15") (pinfunction "A15_A15") (pintype "bidirectional"))
      (node (ref "TP8") (pin "TP") (pinfunction "TP_TP") (pintype "input"))
    )
    (net (code "68") (name "Net-(B2-HV_RXI_2)") (class "Default")
      (node (ref "B1") (pin "34") (pinfunction "34_34") (pintype "bidirectional"))
      (node (ref "B2") (pin "HV3") (pinfunction "HV_RXI_2_HV3") (pintype "bidirectional"))
    )
    (net (code "69") (name "Net-(B2-HV_TXO_2)") (class "Default")
      (node (ref "B1") (pin "35") (pinfunction "35_35") (pintype "bidirectional"))
      (node (ref "B2") (pin "HV4") (pinfunction "HV_TXO_2_HV4") (pintype "bidirectional"))
    )
    (net (code "70") (name "Net-(B2-LV_RXO_2)") (class "Default")
      (node (ref "B2") (pin "LV3") (pinfunction "LV_RXO_2_LV3") (pintype "bidirectional"))
      (node (ref "J8") (pin "7") (pinfunction "GP4_7") (pintype "bidirectional"))
    )
    (net (code "71") (name "Net-(B2-LV_TXI_2)") (class "Default")
      (node (ref "B2") (pin "LV4") (pinfunction "LV_TXI_2_LV4") (pintype "bidirectional"))
      (node (ref "J8") (pin "11") (pinfunction "GP17_11") (pintype "bidirectional"))
    )
    (net (code "72") (name "Net-(J8-CE0)") (class "Default")
      (node (ref "J8") (pin "24") (pinfunction "CE0_24") (pintype "output"))
      (node (ref "TP34") (pin "TP") (pinfunction "TP_TP") (pintype "input"))
    )
    (net (code "73") (name "Net-(J8-CE1)") (class "Default")
      (node (ref "J8") (pin "26") (pinfunction "CE1_26") (pintype "output"))
      (node (ref "TP33") (pin "TP") (pinfunction "TP_TP") (pintype "input"))
    )
    (net (code "74") (name "Net-(J8-GP5)") (class "Default")
      (node (ref "J8") (pin "29") (pinfunction "GP5_29") (pintype "bidirectional"))
      (node (ref "TP54") (pin "TP") (pinfunction "TP_TP") (pintype "input"))
    )
    (net (code "75") (name "Net-(J8-GP6)") (class "Default")
      (node (ref "J8") (pin "31") (pinfunction "GP6_31") (pintype "bidirectional"))
      (node (ref "TP53") (pin "TP") (pinfunction "TP_TP") (pintype "input"))
    )
    (net (code "76") (name "Net-(J8-GP12)") (class "Default")
      (node (ref "J8") (pin "32") (pinfunction "GP12_32") (pintype "bidirectional"))
      (node (ref "TP52") (pin "TP") (pinfunction "TP_TP") (pintype "input"))
    )
    (net (code "77") (name "Net-(J8-GP13)") (class "Default")
      (node (ref "J8") (pin "33") (pinfunction "GP13_33") (pintype "bidirectional"))
      (node (ref "TP51") (pin "TP") (pinfunction "TP_TP") (pintype "input"))
    )
    (net (code "78") (name "Net-(J8-GP16)") (class "Default")
      (node (ref "J8") (pin "36") (pinfunction "GP16_36") (pintype "bidirectional"))
      (node (ref "TP50") (pin "TP") (pinfunction "TP_TP") (pintype "input"))
    )
    (net (code "79") (name "Net-(J8-GP18#)") (class "Default")
      (node (ref "J8") (pin "12") (pinfunction "GP18#_12") (pintype "bidirectional"))
      (node (ref "TP40") (pin "TP") (pinfunction "TP_TP") (pintype "input"))
    )
    (net (code "80") (name "Net-(J8-GP19)") (class "Default")
      (node (ref "J8") (pin "35") (pinfunction "GP19_35") (pintype "bidirectional"))
      (node (ref "TP49") (pin "TP") (pinfunction "TP_TP") (pintype "input"))
    )
    (net (code "81") (name "Net-(J8-GP20)") (class "Default")
      (node (ref "J8") (pin "38") (pinfunction "GP20_38") (pintype "bidirectional"))
      (node (ref "TP48") (pin "TP") (pinfunction "TP_TP") (pintype "input"))
    )
    (net (code "82") (name "Net-(J8-GP21)") (class "Default")
      (node (ref "J8") (pin "40") (pinfunction "GP21_40") (pintype "bidirectional"))
      (node (ref "TP47") (pin "TP") (pinfunction "TP_TP") (pintype "input"))
    )
    (net (code "83") (name "Net-(J8-GP22)") (class "Default")
      (node (ref "J8") (pin "15") (pinfunction "GP22_15") (pintype "bidirectional"))
      (node (ref "TP41") (pin "TP") (pinfunction "TP_TP") (pintype "input"))
    )
    (net (code "84") (name "Net-(J8-GP23)") (class "Default")
      (node (ref "J8") (pin "16") (pinfunction "GP23_16") (pintype "bidirectional"))
      (node (ref "TP42") (pin "TP") (pinfunction "TP_TP") (pintype "input"))
    )
    (net (code "85") (name "Net-(J8-GP24)") (class "Default")
      (node (ref "J8") (pin "18") (pinfunction "GP24_18") (pintype "bidirectional"))
      (node (ref "TP43") (pin "TP") (pinfunction "TP_TP") (pintype "input"))
    )
    (net (code "86") (name "Net-(J8-GP25)") (class "Default")
      (node (ref "J8") (pin "22") (pinfunction "GP25_22") (pintype "bidirectional"))
      (node (ref "TP44") (pin "TP") (pinfunction "TP_TP") (pintype "input"))
    )
    (net (code "87") (name "Net-(J8-GP26)") (class "Default")
      (node (ref "J8") (pin "37") (pinfunction "GP26_37") (pintype "bidirectional"))
      (node (ref "TP46") (pin "TP") (pinfunction "TP_TP") (pintype "input"))
    )
    (net (code "88") (name "Net-(J8-GP27)") (class "Default")
      (node (ref "J8") (pin "13") (pinfunction "GP27_13") (pintype "bidirectional"))
      (node (ref "TP45") (pin "TP") (pinfunction "TP_TP") (pintype "input"))
    )
    (net (code "89") (name "Net-(J8-MISO)") (class "Default")
      (node (ref "J8") (pin "21") (pinfunction "MISO_21") (pintype "input"))
      (node (ref "TP36") (pin "TP") (pinfunction "TP_TP") (pintype "input"))
    )
    (net (code "90") (name "Net-(J8-MOSI)") (class "Default")
      (node (ref "J8") (pin "19") (pinfunction "MOSI_19") (pintype "output"))
      (node (ref "TP35") (pin "TP") (pinfunction "TP_TP") (pintype "input"))
    )
    (net (code "91") (name "Net-(J8-RXI)") (class "Default")
      (node (ref "J8") (pin "10") (pinfunction "RXI_10") (pintype "input"))
      (node (ref "TP39") (pin "TP") (pinfunction "TP_TP") (pintype "input"))
    )
    (net (code "92") (name "Net-(J8-SCLK)") (class "Default")
      (node (ref "J8") (pin "23") (pinfunction "SCLK_23") (pintype "output"))
      (node (ref "TP37") (pin "TP") (pinfunction "TP_TP") (pintype "input"))
    )
    (net (code "93") (name "Net-(J8-TXO)") (class "Default")
      (node (ref "J8") (pin "8") (pinfunction "TXO_8") (pintype "output"))
      (node (ref "TP38") (pin "TP") (pinfunction "TP_TP") (pintype "input"))
    )
    (net (code "94") (name "Net-(LS1-1)") (class "Default")
      (node (ref "B1") (pin "53") (pinfunction "53_53") (pintype "bidirectional"))
      (node (ref "LS1") (pin "+") (pinfunction "1_+") (pintype "passive"))
    )
    (net (code "95") (name "Net-(M1-SIG)") (class "Default")
      (node (ref "B1") (pin "5") (pinfunction "5_5") (pintype "bidirectional"))
      (node (ref "M1") (pin "1") (pinfunction "SIG_1") (pintype "bidirectional"))
      (node (ref "TP58") (pin "TP") (pinfunction "TP_TP") (pintype "input"))
    )
    (net (code "96") (name "Net-(M2-SIG)") (class "Default")
      (node (ref "B1") (pin "4") (pinfunction "4_4") (pintype "bidirectional"))
      (node (ref "M2") (pin "1") (pinfunction "SIG_1") (pintype "bidirectional"))
      (node (ref "TP57") (pin "TP") (pinfunction "TP_TP") (pintype "input"))
    )
    (net (code "97") (name "Net-(M3-SIG)") (class "Default")
      (node (ref "B1") (pin "3") (pinfunction "3_3") (pintype "bidirectional"))
      (node (ref "M3") (pin "1") (pinfunction "SIG_1") (pintype "bidirectional"))
      (node (ref "TP56") (pin "TP") (pinfunction "TP_TP") (pintype "input"))
    )
    (net (code "98") (name "Net-(M4-SIG)") (class "Default")
      (node (ref "B1") (pin "2") (pinfunction "2_2") (pintype "bidirectional"))
      (node (ref "M4") (pin "1") (pinfunction "SIG_1") (pintype "bidirectional"))
      (node (ref "TP55") (pin "TP") (pinfunction "TP_TP") (pintype "input"))
    )
    (net (code "99") (name "Net-(M5-SIG)") (class "Default")
      (node (ref "B1") (pin "13") (pinfunction "13_13") (pintype "bidirectional"))
      (node (ref "M5") (pin "1") (pinfunction "SIG_1") (pintype "bidirectional"))
    )
    (net (code "100") (name "Net-(M6-SIG)") (class "Default")
      (node (ref "B1") (pin "12") (pinfunction "12_12") (pintype "bidirectional"))
      (node (ref "M6") (pin "1") (pinfunction "SIG_1") (pintype "bidirectional"))
    )
    (net (code "101") (name "Net-(S1-O)") (class "Default")
      (node (ref "J4") (pin "2") (pinfunction "2_2") (pintype "passive"))
      (node (ref "S1") (pin "1") (pinfunction "O_1") (pintype "passive"))
    )
    (net (code "102") (name "unconnected-(B1-Pad3.3V)") (class "Default")
      (node (ref "B1") (pin "3.3V") (pinfunction "3.3V_3.3V") (pintype "bidirectional"))
    )
    (net (code "103") (name "unconnected-(B1-Pad52)") (class "Default")
      (node (ref "B1") (pin "52") (pinfunction "52_52") (pintype "bidirectional"))
    )
    (net (code "104") (name "unconnected-(B1-PadAREF)") (class "Default")
      (node (ref "B1") (pin "AREF") (pinfunction "AREF_AREF") (pintype "bidirectional"))
    )
    (net (code "105") (name "unconnected-(B1-PadRESET)") (class "Default")
      (node (ref "B1") (pin "RESET") (pinfunction "RESET_RESET") (pintype "bidirectional"))
    )
    (net (code "106") (name "unconnected-(B1-PadVIN)") (class "Default")
      (node (ref "B1") (pin "VIN") (pinfunction "VIN_VIN") (pintype "bidirectional"))
    )
    (net (code "107") (name "unconnected-(J1-Pad1)") (class "Default")
      (node (ref "J1") (pin "1") (pinfunction "1_1") (pintype "passive"))
    )
    (net (code "108") (name "unconnected-(J1-Pad15)") (class "Default")
      (node (ref "J1") (pin "15") (pinfunction "15_15") (pintype "passive"))
    )
    (net (code "109") (name "unconnected-(J2-Pad1)") (class "Default")
      (node (ref "J2") (pin "1") (pinfunction "1_1") (pintype "passive"))
    )
    (net (code "110") (name "unconnected-(J2-Pad15)") (class "Default")
      (node (ref "J2") (pin "15") (pinfunction "15_15") (pintype "passive"))
    )
    (net (code "111") (name "unconnected-(J3-Pad1)") (class "Default")
      (node (ref "J3") (pin "1") (pinfunction "1_1") (pintype "passive"))
    )
    (net (code "112") (name "unconnected-(J3-Pad15)") (class "Default")
      (node (ref "J3") (pin "15") (pinfunction "15_15") (pintype "passive"))
    )
    (net (code "113") (name "unconnected-(J8-ID_SC-Pad28)") (class "Default")
      (node (ref "J8") (pin "28") (pinfunction "ID_SC_28") (pintype "bidirectional"))
    )
    (net (code "114") (name "unconnected-(J8-ID_SD-Pad27)") (class "Default")
      (node (ref "J8") (pin "27") (pinfunction "ID_SD_27") (pintype "bidirectional"))
    )
    (net (code "115") (name "unconnected-(J9-Pad1)") (class "Default")
      (node (ref "J9") (pin "1") (pinfunction "1_1") (pintype "bidirectional"))
    )
    (net (code "116") (name "unconnected-(J9-Pad2)") (class "Default")
      (node (ref "J9") (pin "2") (pinfunction "2_2") (pintype "bidirectional"))
    )
    (net (code "117") (name "unconnected-(J9-Pad3)") (class "Default")
      (node (ref "J9") (pin "3") (pinfunction "3_3") (pintype "bidirectional"))
    )
    (net (code "118") (name "unconnected-(J9-Pad4)") (class "Default")
      (node (ref "J9") (pin "4") (pinfunction "4_4") (pintype "bidirectional"))
    )
    (net (code "119") (name "unconnected-(J9-Pad5)") (class "Default")
      (node (ref "J9") (pin "5") (pinfunction "5_5") (pintype "bidirectional"))
    )
    (net (code "120") (name "unconnected-(J9-Pad6)") (class "Default")
      (node (ref "J9") (pin "6") (pinfunction "6_6") (pintype "bidirectional"))
    )
    (net (code "121") (name "unconnected-(J10-Pad1)") (class "Default")
      (node (ref "J10") (pin "1") (pinfunction "1_1") (pintype "bidirectional"))
    )
    (net (code "122") (name "unconnected-(J10-Pad2)") (class "Default")
      (node (ref "J10") (pin "2") (pinfunction "2_2") (pintype "bidirectional"))
    )
    (net (code "123") (name "unconnected-(J10-Pad3)") (class "Default")
      (node (ref "J10") (pin "3") (pinfunction "3_3") (pintype "bidirectional"))
    )
    (net (code "124") (name "unconnected-(J10-Pad4)") (class "Default")
      (node (ref "J10") (pin "4") (pinfunction "4_4") (pintype "bidirectional"))
    )
    (net (code "125") (name "unconnected-(J10-Pad5)") (class "Default")
      (node (ref "J10") (pin "5") (pinfunction "5_5") (pintype "bidirectional"))
    )
    (net (code "126") (name "unconnected-(J10-Pad6)") (class "Default")
      (node (ref "J10") (pin "6") (pinfunction "6_6") (pintype "bidirectional"))
    )
    (net (code "127") (name "unconnected-(J11-Pad1)") (class "Default")
      (node (ref "J11") (pin "1") (pinfunction "1_1") (pintype "bidirectional"))
    )
    (net (code "128") (name "unconnected-(J11-Pad2)") (class "Default")
      (node (ref "J11") (pin "2") (pinfunction "2_2") (pintype "bidirectional"))
    )
    (net (code "129") (name "unconnected-(J11-Pad3)") (class "Default")
      (node (ref "J11") (pin "3") (pinfunction "3_3") (pintype "bidirectional"))
    )
    (net (code "130") (name "unconnected-(J11-Pad4)") (class "Default")
      (node (ref "J11") (pin "4") (pinfunction "4_4") (pintype "bidirectional"))
    )
    (net (code "131") (name "unconnected-(J11-Pad5)") (class "Default")
      (node (ref "J11") (pin "5") (pinfunction "5_5") (pintype "bidirectional"))
    )
    (net (code "132") (name "unconnected-(J11-Pad6)") (class "Default")
      (node (ref "J11") (pin "6") (pinfunction "6_6") (pintype "bidirectional"))
    )
    (net (code "133") (name "unconnected-(J12-Pad1)") (class "Default")
      (node (ref "J12") (pin "1") (pinfunction "1_1") (pintype "bidirectional"))
    )
    (net (code "134") (name "unconnected-(J12-Pad2)") (class "Default")
      (node (ref "J12") (pin "2") (pinfunction "2_2") (pintype "bidirectional"))
    )
    (net (code "135") (name "unconnected-(J12-Pad3)") (class "Default")
      (node (ref "J12") (pin "3") (pinfunction "3_3") (pintype "bidirectional"))
    )
    (net (code "136") (name "unconnected-(J12-Pad4)") (class "Default")
      (node (ref "J12") (pin "4") (pinfunction "4_4") (pintype "bidirectional"))
    )
    (net (code "137") (name "unconnected-(J12-Pad5)") (class "Default")
      (node (ref "J12") (pin "5") (pinfunction "5_5") (pintype "bidirectional"))
    )
    (net (code "138") (name "unconnected-(J12-Pad6)") (class "Default")
      (node (ref "J12") (pin "6") (pinfunction "6_6") (pintype "bidirectional"))
    )
    (net (code "139") (name "unconnected-(J13-Pad1)") (class "Default")
      (node (ref "J13") (pin "1") (pinfunction "1_1") (pintype "bidirectional"))
    )
    (net (code "140") (name "unconnected-(J13-Pad2)") (class "Default")
      (node (ref "J13") (pin "2") (pinfunction "2_2") (pintype "bidirectional"))
    )
    (net (code "141") (name "unconnected-(J13-Pad3)") (class "Default")
      (node (ref "J13") (pin "3") (pinfunction "3_3") (pintype "bidirectional"))
    )
    (net (code "142") (name "unconnected-(J13-Pad4)") (class "Default")
      (node (ref "J13") (pin "4") (pinfunction "4_4") (pintype "bidirectional"))
    )
    (net (code "143") (name "unconnected-(J13-Pad5)") (class "Default")
      (node (ref "J13") (pin "5") (pinfunction "5_5") (pintype "bidirectional"))
    )
    (net (code "144") (name "unconnected-(J13-Pad6)") (class "Default")
      (node (ref "J13") (pin "6") (pinfunction "6_6") (pintype "bidirectional"))
    )
    (net (code "145") (name "unconnected-(J14-Pad1)") (class "Default")
      (node (ref "J14") (pin "1") (pinfunction "1_1") (pintype "bidirectional"))
    )
    (net (code "146") (name "unconnected-(J14-Pad2)") (class "Default")
      (node (ref "J14") (pin "2") (pinfunction "2_2") (pintype "bidirectional"))
    )
    (net (code "147") (name "unconnected-(J14-Pad3)") (class "Default")
      (node (ref "J14") (pin "3") (pinfunction "3_3") (pintype "bidirectional"))
    )
    (net (code "148") (name "unconnected-(J14-Pad4)") (class "Default")
      (node (ref "J14") (pin "4") (pinfunction "4_4") (pintype "bidirectional"))
    )
    (net (code "149") (name "unconnected-(J14-Pad5)") (class "Default")
      (node (ref "J14") (pin "5") (pinfunction "5_5") (pintype "bidirectional"))
    )
    (net (code "150") (name "unconnected-(J14-Pad6)") (class "Default")
      (node (ref "J14") (pin "6") (pinfunction "6_6") (pintype "bidirectional"))
    )
    (net (code "151") (name "unconnected-(J15-Pad1)") (class "Default")
      (node (ref "J15") (pin "1") (pinfunction "1_1") (pintype "bidirectional"))
    )
    (net (code "152") (name "unconnected-(J15-Pad2)") (class "Default")
      (node (ref "J15") (pin "2") (pinfunction "2_2") (pintype "bidirectional"))
    )
    (net (code "153") (name "unconnected-(J15-Pad3)") (class "Default")
      (node (ref "J15") (pin "3") (pinfunction "3_3") (pintype "bidirectional"))
    )
    (net (code "154") (name "unconnected-(J15-Pad4)") (class "Default")
      (node (ref "J15") (pin "4") (pinfunction "4_4") (pintype "bidirectional"))
    )
    (net (code "155") (name "unconnected-(J15-Pad5)") (class "Default")
      (node (ref "J15") (pin "5") (pinfunction "5_5") (pintype "bidirectional"))
    )
    (net (code "156") (name "unconnected-(J15-Pad6)") (class "Default")
      (node (ref "J15") (pin "6") (pinfunction "6_6") (pintype "bidirectional"))
    )
    (net (code "157") (name "unconnected-(J16-Pad1)") (class "Default")
      (node (ref "J16") (pin "1") (pinfunction "1_1") (pintype "bidirectional"))
    )
    (net (code "158") (name "unconnected-(J16-Pad2)") (class "Default")
      (node (ref "J16") (pin "2") (pinfunction "2_2") (pintype "bidirectional"))
    )
    (net (code "159") (name "unconnected-(J16-Pad3)") (class "Default")
      (node (ref "J16") (pin "3") (pinfunction "3_3") (pintype "bidirectional"))
    )
    (net (code "160") (name "unconnected-(J16-Pad4)") (class "Default")
      (node (ref "J16") (pin "4") (pinfunction "4_4") (pintype "bidirectional"))
    )
    (net (code "161") (name "unconnected-(J16-Pad5)") (class "Default")
      (node (ref "J16") (pin "5") (pinfunction "5_5") (pintype "bidirectional"))
    )
    (net (code "162") (name "unconnected-(J16-Pad6)") (class "Default")
      (node (ref "J16") (pin "6") (pinfunction "6_6") (pintype "bidirectional"))
    )
    (net (code "163") (name "unconnected-(J18-Pad1)") (class "Default")
      (node (ref "J18") (pin "1") (pinfunction "1_1") (pintype "passive"))
    )
    (net (code "164") (name "unconnected-(J18-Pad2)") (class "Default")
      (node (ref "J18") (pin "2") (pinfunction "2_2") (pintype "passive"))
    )
    (net (code "165") (name "unconnected-(J18-Pad3)") (class "Default")
      (node (ref "J18") (pin "3") (pinfunction "3_3") (pintype "passive"))
    )
    (net (code "166") (name "unconnected-(J18-Pad4)") (class "Default")
      (node (ref "J18") (pin "4") (pinfunction "4_4") (pintype "passive"))
    )
    (net (code "167") (name "unconnected-(J18-Pad5)") (class "Default")
      (node (ref "J18") (pin "5") (pinfunction "5_5") (pintype "passive"))
    )
    (net (code "168") (name "unconnected-(J18-Pad6)") (class "Default")
      (node (ref "J18") (pin "6") (pinfunction "6_6") (pintype "passive"))
    )
    (net (code "169") (name "unconnected-(J18-Pad7)") (class "Default")
      (node (ref "J18") (pin "7") (pinfunction "7_7") (pintype "passive"))
    )
    (net (code "170") (name "unconnected-(J18-Pad8)") (class "Default")
      (node (ref "J18") (pin "8") (pinfunction "8_8") (pintype "passive"))
    )
    (net (code "171") (name "unconnected-(J19-Pad1)") (class "Default")
      (node (ref "J19") (pin "1") (pinfunction "1_1") (pintype "passive"))
    )
    (net (code "172") (name "unconnected-(J19-Pad2)") (class "Default")
      (node (ref "J19") (pin "2") (pinfunction "2_2") (pintype "passive"))
    )
    (net (code "173") (name "unconnected-(J19-Pad3)") (class "Default")
      (node (ref "J19") (pin "3") (pinfunction "3_3") (pintype "passive"))
    )
    (net (code "174") (name "unconnected-(J19-Pad4)") (class "Default")
      (node (ref "J19") (pin "4") (pinfunction "4_4") (pintype "passive"))
    )
    (net (code "175") (name "unconnected-(J19-Pad5)") (class "Default")
      (node (ref "J19") (pin "5") (pinfunction "5_5") (pintype "passive"))
    )
    (net (code "176") (name "unconnected-(J19-Pad6)") (class "Default")
      (node (ref "J19") (pin "6") (pinfunction "6_6") (pintype "passive"))
    )
    (net (code "177") (name "unconnected-(J19-Pad7)") (class "Default")
      (node (ref "J19") (pin "7") (pinfunction "7_7") (pintype "passive"))
    )
    (net (code "178") (name "unconnected-(J19-Pad8)") (class "Default")
      (node (ref "J19") (pin "8") (pinfunction "8_8") (pintype "passive"))
    )
    (net (code "179") (name "unconnected-(J20-Pad1)") (class "Default")
      (node (ref "J20") (pin "1") (pinfunction "1_1") (pintype "passive"))
    )
    (net (code "180") (name "unconnected-(J20-Pad2)") (class "Default")
      (node (ref "J20") (pin "2") (pinfunction "2_2") (pintype "passive"))
    )
    (net (code "181") (name "unconnected-(J20-Pad3)") (class "Default")
      (node (ref "J20") (pin "3") (pinfunction "3_3") (pintype "passive"))
    )
    (net (code "182") (name "unconnected-(J20-Pad4)") (class "Default")
      (node (ref "J20") (pin "4") (pinfunction "4_4") (pintype "passive"))
    )
    (net (code "183") (name "unconnected-(J20-Pad5)") (class "Default")
      (node (ref "J20") (pin "5") (pinfunction "5_5") (pintype "passive"))
    )
    (net (code "184") (name "unconnected-(J20-Pad6)") (class "Default")
      (node (ref "J20") (pin "6") (pinfunction "6_6") (pintype "passive"))
    )
    (net (code "185") (name "unconnected-(J20-Pad7)") (class "Default")
      (node (ref "J20") (pin "7") (pinfunction "7_7") (pintype "passive"))
    )
    (net (code "186") (name "unconnected-(J20-Pad8)") (class "Default")
      (node (ref "J20") (pin "8") (pinfunction "8_8") (pintype "passive"))
    )
    (net (code "187") (name "unconnected-(J21-Pad1)") (class "Default")
      (node (ref "J21") (pin "1") (pinfunction "1_1") (pintype "passive"))
    )
    (net (code "188") (name "unconnected-(J21-Pad2)") (class "Default")
      (node (ref "J21") (pin "2") (pinfunction "2_2") (pintype "passive"))
    )
    (net (code "189") (name "unconnected-(J21-Pad3)") (class "Default")
      (node (ref "J21") (pin "3") (pinfunction "3_3") (pintype "passive"))
    )
    (net (code "190") (name "unconnected-(J21-Pad4)") (class "Default")
      (node (ref "J21") (pin "4") (pinfunction "4_4") (pintype "passive"))
    )
    (net (code "191") (name "unconnected-(J21-Pad5)") (class "Default")
      (node (ref "J21") (pin "5") (pinfunction "5_5") (pintype "passive"))
    )
    (net (code "192") (name "unconnected-(J21-Pad6)") (class "Default")
      (node (ref "J21") (pin "6") (pinfunction "6_6") (pintype "passive"))
    )
    (net (code "193") (name "unconnected-(J21-Pad7)") (class "Default")
      (node (ref "J21") (pin "7") (pinfunction "7_7") (pintype "passive"))
    )
    (net (code "194") (name "unconnected-(J21-Pad8)") (class "Default")
      (node (ref "J21") (pin "8") (pinfunction "8_8") (pintype "passive"))
    )
    (net (code "195") (name "unconnected-(J22-Pad1)") (class "Default")
      (node (ref "J22") (pin "1") (pinfunction "1_1") (pintype "passive"))
    )
    (net (code "196") (name "unconnected-(J22-Pad2)") (class "Default")
      (node (ref "J22") (pin "2") (pinfunction "2_2") (pintype "passive"))
    )
    (net (code "197") (name "unconnected-(J22-Pad3)") (class "Default")
      (node (ref "J22") (pin "3") (pinfunction "3_3") (pintype "passive"))
    )
    (net (code "198") (name "unconnected-(J22-Pad4)") (class "Default")
      (node (ref "J22") (pin "4") (pinfunction "4_4") (pintype "passive"))
    )
    (net (code "199") (name "unconnected-(J22-Pad5)") (class "Default")
      (node (ref "J22") (pin "5") (pinfunction "5_5") (pintype "passive"))
    )
    (net (code "200") (name "unconnected-(J22-Pad6)") (class "Default")
      (node (ref "J22") (pin "6") (pinfunction "6_6") (pintype "passive"))
    )
    (net (code "201") (name "unconnected-(J22-Pad7)") (class "Default")
      (node (ref "J22") (pin "7") (pinfunction "7_7") (pintype "passive"))
    )
    (net (code "202") (name "unconnected-(J22-Pad8)") (class "Default")
      (node (ref "J22") (pin "8") (pinfunction "8_8") (pintype "passive"))
    )
    (net (code "203") (name "unconnected-(J23-Pad1)") (class "Default")
      (node (ref "J23") (pin "1") (pinfunction "1_1") (pintype "passive"))
    )
    (net (code "204") (name "unconnected-(J23-Pad2)") (class "Default")
      (node (ref "J23") (pin "2") (pinfunction "2_2") (pintype "passive"))
    )
    (net (code "205") (name "unconnected-(J23-Pad3)") (class "Default")
      (node (ref "J23") (pin "3") (pinfunction "3_3") (pintype "passive"))
    )
    (net (code "206") (name "unconnected-(J23-Pad4)") (class "Default")
      (node (ref "J23") (pin "4") (pinfunction "4_4") (pintype "passive"))
    )
    (net (code "207") (name "unconnected-(J23-Pad5)") (class "Default")
      (node (ref "J23") (pin "5") (pinfunction "5_5") (pintype "passive"))
    )
    (net (code "208") (name "unconnected-(J23-Pad6)") (class "Default")
      (node (ref "J23") (pin "6") (pinfunction "6_6") (pintype "passive"))
    )
    (net (code "209") (name "unconnected-(J23-Pad7)") (class "Default")
      (node (ref "J23") (pin "7") (pinfunction "7_7") (pintype "passive"))
    )
    (net (code "210") (name "unconnected-(J23-Pad8)") (class "Default")
      (node (ref "J23") (pin "8") (pinfunction "8_8") (pintype "passive"))
    )
    (net (code "211") (name "unconnected-(J24-Pad1)") (class "Default")
      (node (ref "J24") (pin "1") (pinfunction "1_1") (pintype "passive"))
    )
    (net (code "212") (name "unconnected-(J24-Pad2)") (class "Default")
      (node (ref "J24") (pin "2") (pinfunction "2_2") (pintype "passive"))
    )
    (net (code "213") (name "unconnected-(J24-Pad3)") (class "Default")
      (node (ref "J24") (pin "3") (pinfunction "3_3") (pintype "passive"))
    )
    (net (code "214") (name "unconnected-(J24-Pad4)") (class "Default")
      (node (ref "J24") (pin "4") (pinfunction "4_4") (pintype "passive"))
    )
    (net (code "215") (name "unconnected-(J24-Pad5)") (class "Default")
      (node (ref "J24") (pin "5") (pinfunction "5_5") (pintype "passive"))
    )
    (net (code "216") (name "unconnected-(J24-Pad6)") (class "Default")
      (node (ref "J24") (pin "6") (pinfunction "6_6") (pintype "passive"))
    )
    (net (code "217") (name "unconnected-(J24-Pad7)") (class "Default")
      (node (ref "J24") (pin "7") (pinfunction "7_7") (pintype "passive"))
    )
    (net (code "218") (name "unconnected-(J24-Pad8)") (class "Default")
      (node (ref "J24") (pin "8") (pinfunction "8_8") (pintype "passive"))
    )
    (net (code "219") (name "unconnected-(J25-Pad1)") (class "Default")
      (node (ref "J25") (pin "1") (pinfunction "1_1") (pintype "passive"))
    )
    (net (code "220") (name "unconnected-(J25-Pad2)") (class "Default")
      (node (ref "J25") (pin "2") (pinfunction "2_2") (pintype "passive"))
    )
    (net (code "221") (name "unconnected-(J25-Pad3)") (class "Default")
      (node (ref "J25") (pin "3") (pinfunction "3_3") (pintype "passive"))
    )
    (net (code "222") (name "unconnected-(J25-Pad4)") (class "Default")
      (node (ref "J25") (pin "4") (pinfunction "4_4") (pintype "passive"))
    )
    (net (code "223") (name "unconnected-(J25-Pad5)") (class "Default")
      (node (ref "J25") (pin "5") (pinfunction "5_5") (pintype "passive"))
    )
    (net (code "224") (name "unconnected-(J25-Pad6)") (class "Default")
      (node (ref "J25") (pin "6") (pinfunction "6_6") (pintype "passive"))
    )
    (net (code "225") (name "unconnected-(J25-Pad7)") (class "Default")
      (node (ref "J25") (pin "7") (pinfunction "7_7") (pintype "passive"))
    )
    (net (code "226") (name "unconnected-(J25-Pad8)") (class "Default")
      (node (ref "J25") (pin "8") (pinfunction "8_8") (pintype "passive"))
    )
    (net (code "227") (name "unconnected-(J26-Pad1)") (class "Default")
      (node (ref "J26") (pin "1") (pinfunction "1_1") (pintype "passive"))
    )
    (net (code "228") (name "unconnected-(J26-Pad2)") (class "Default")
      (node (ref "J26") (pin "2") (pinfunction "2_2") (pintype "passive"))
    )
    (net (code "229") (name "unconnected-(J26-Pad3)") (class "Default")
      (node (ref "J26") (pin "3") (pinfunction "3_3") (pintype "passive"))
    )
    (net (code "230") (name "unconnected-(J26-Pad4)") (class "Default")
      (node (ref "J26") (pin "4") (pinfunction "4_4") (pintype "passive"))
    )
    (net (code "231") (name "unconnected-(J26-Pad5)") (class "Default")
      (node (ref "J26") (pin "5") (pinfunction "5_5") (pintype "passive"))
    )
    (net (code "232") (name "unconnected-(J26-Pad6)") (class "Default")
      (node (ref "J26") (pin "6") (pinfunction "6_6") (pintype "passive"))
    )
    (net (code "233") (name "unconnected-(J26-Pad7)") (class "Default")
      (node (ref "J26") (pin "7") (pinfunction "7_7") (pintype "passive"))
    )
    (net (code "234") (name "unconnected-(J26-Pad8)") (class "Default")
      (node (ref "J26") (pin "8") (pinfunction "8_8") (pintype "passive"))
    )
    (net (code "235") (name "unconnected-(J27-Pad1)") (class "Default")
      (node (ref "J27") (pin "1") (pinfunction "1_1") (pintype "passive"))
    )
    (net (code "236") (name "unconnected-(J27-Pad2)") (class "Default")
      (node (ref "J27") (pin "2") (pinfunction "2_2") (pintype "passive"))
    )
    (net (code "237") (name "unconnected-(J27-Pad3)") (class "Default")
      (node (ref "J27") (pin "3") (pinfunction "3_3") (pintype "passive"))
    )
    (net (code "238") (name "unconnected-(J27-Pad4)") (class "Default")
      (node (ref "J27") (pin "4") (pinfunction "4_4") (pintype "passive"))
    )
    (net (code "239") (name "unconnected-(J27-Pad5)") (class "Default")
      (node (ref "J27") (pin "5") (pinfunction "5_5") (pintype "passive"))
    )
    (net (code "240") (name "unconnected-(J27-Pad6)") (class "Default")
      (node (ref "J27") (pin "6") (pinfunction "6_6") (pintype "passive"))
    )
    (net (code "241") (name "unconnected-(J27-Pad7)") (class "Default")
      (node (ref "J27") (pin "7") (pinfunction "7_7") (pintype "passive"))
    )
    (net (code "242") (name "unconnected-(J27-Pad8)") (class "Default")
      (node (ref "J27") (pin "8") (pinfunction "8_8") (pintype "passive"))
    )
    (net (code "243") (name "unconnected-(J28-Pad1)") (class "Default")
      (node (ref "J28") (pin "1") (pinfunction "1_1") (pintype "passive"))
    )
    (net (code "244") (name "unconnected-(J28-Pad2)") (class "Default")
      (node (ref "J28") (pin "2") (pinfunction "2_2") (pintype "passive"))
    )
    (net (code "245") (name "unconnected-(J28-Pad3)") (class "Default")
      (node (ref "J28") (pin "3") (pinfunction "3_3") (pintype "passive"))
    )
    (net (code "246") (name "unconnected-(J28-Pad4)") (class "Default")
      (node (ref "J28") (pin "4") (pinfunction "4_4") (pintype "passive"))
    )
    (net (code "247") (name "unconnected-(J28-Pad5)") (class "Default")
      (node (ref "J28") (pin "5") (pinfunction "5_5") (pintype "passive"))
    )
    (net (code "248") (name "unconnected-(J28-Pad6)") (class "Default")
      (node (ref "J28") (pin "6") (pinfunction "6_6") (pintype "passive"))
    )
    (net (code "249") (name "unconnected-(J28-Pad7)") (class "Default")
      (node (ref "J28") (pin "7") (pinfunction "7_7") (pintype "passive"))
    )
    (net (code "250") (name "unconnected-(J28-Pad8)") (class "Default")
      (node (ref "J28") (pin "8") (pinfunction "8_8") (pintype "passive"))
    )
    (net (code "251") (name "unconnected-(J29-Pad1)") (class "Default")
      (node (ref "J29") (pin "1") (pinfunction "1_1") (pintype "passive"))
    )
    (net (code "252") (name "unconnected-(J29-Pad2)") (class "Default")
      (node (ref "J29") (pin "2") (pinfunction "2_2") (pintype "passive"))
    )
    (net (code "253") (name "unconnected-(J29-Pad3)") (class "Default")
      (node (ref "J29") (pin "3") (pinfunction "3_3") (pintype "passive"))
    )
    (net (code "254") (name "unconnected-(J29-Pad4)") (class "Default")
      (node (ref "J29") (pin "4") (pinfunction "4_4") (pintype "passive"))
    )
    (net (code "255") (name "unconnected-(J29-Pad5)") (class "Default")
      (node (ref "J29") (pin "5") (pinfunction "5_5") (pintype "passive"))
    )
    (net (code "256") (name "unconnected-(J29-Pad6)") (class "Default")
      (node (ref "J29") (pin "6") (pinfunction "6_6") (pintype "passive"))
    )
    (net (code "257") (name "unconnected-(J29-Pad7)") (class "Default")
      (node (ref "J29") (pin "7") (pinfunction "7_7") (pintype "passive"))
    )
    (net (code "258") (name "unconnected-(J29-Pad8)") (class "Default")
      (node (ref "J29") (pin "8") (pinfunction "8_8") (pintype "passive"))
    )
    (net (code "259") (name "unconnected-(J30-Pad1)") (class "Default")
      (node (ref "J30") (pin "1") (pinfunction "1_1") (pintype "passive"))
    )
    (net (code "260") (name "unconnected-(J30-Pad2)") (class "Default")
      (node (ref "J30") (pin "2") (pinfunction "2_2") (pintype "passive"))
    )
    (net (code "261") (name "unconnected-(J30-Pad3)") (class "Default")
      (node (ref "J30") (pin "3") (pinfunction "3_3") (pintype "passive"))
    )
    (net (code "262") (name "unconnected-(J30-Pad4)") (class "Default")
      (node (ref "J30") (pin "4") (pinfunction "4_4") (pintype "passive"))
    )
    (net (code "263") (name "unconnected-(J30-Pad5)") (class "Default")
      (node (ref "J30") (pin "5") (pinfunction "5_5") (pintype "passive"))
    )
    (net (code "264") (name "unconnected-(J30-Pad6)") (class "Default")
      (node (ref "J30") (pin "6") (pinfunction "6_6") (pintype "passive"))
    )
    (net (code "265") (name "unconnected-(J30-Pad7)") (class "Default")
      (node (ref "J30") (pin "7") (pinfunction "7_7") (pintype "passive"))
    )
    (net (code "266") (name "unconnected-(J30-Pad8)") (class "Default")
      (node (ref "J30") (pin "8") (pinfunction "8_8") (pintype "passive"))
    )
    (net (code "267") (name "unconnected-(J31-Pad1)") (class "Default")
      (node (ref "J31") (pin "1") (pinfunction "1_1") (pintype "passive"))
    )
    (net (code "268") (name "unconnected-(J31-Pad2)") (class "Default")
      (node (ref "J31") (pin "2") (pinfunction "2_2") (pintype "passive"))
    )
    (net (code "269") (name "unconnected-(J31-Pad3)") (class "Default")
      (node (ref "J31") (pin "3") (pinfunction "3_3") (pintype "passive"))
    )
    (net (code "270") (name "unconnected-(J31-Pad4)") (class "Default")
      (node (ref "J31") (pin "4") (pinfunction "4_4") (pintype "passive"))
    )
    (net (code "271") (name "unconnected-(J31-Pad5)") (class "Default")
      (node (ref "J31") (pin "5") (pinfunction "5_5") (pintype "passive"))
    )
    (net (code "272") (name "unconnected-(J31-Pad6)") (class "Default")
      (node (ref "J31") (pin "6") (pinfunction "6_6") (pintype "passive"))
    )
    (net (code "273") (name "unconnected-(J31-Pad7)") (class "Default")
      (node (ref "J31") (pin "7") (pinfunction "7_7") (pintype "passive"))
    )
    (net (code "274") (name "unconnected-(J31-Pad8)") (class "Default")
      (node (ref "J31") (pin "8") (pinfunction "8_8") (pintype "passive"))
    )
    (net (code "275") (name "unconnected-(J32-Pad1)") (class "Default")
      (node (ref "J32") (pin "1") (pinfunction "1_1") (pintype "passive"))
    )
    (net (code "276") (name "unconnected-(J32-Pad2)") (class "Default")
      (node (ref "J32") (pin "2") (pinfunction "2_2") (pintype "passive"))
    )
    (net (code "277") (name "unconnected-(J32-Pad3)") (class "Default")
      (node (ref "J32") (pin "3") (pinfunction "3_3") (pintype "passive"))
    )
    (net (code "278") (name "unconnected-(J32-Pad4)") (class "Default")
      (node (ref "J32") (pin "4") (pinfunction "4_4") (pintype "passive"))
    )
    (net (code "279") (name "unconnected-(J32-Pad5)") (class "Default")
      (node (ref "J32") (pin "5") (pinfunction "5_5") (pintype "passive"))
    )
    (net (code "280") (name "unconnected-(J32-Pad6)") (class "Default")
      (node (ref "J32") (pin "6") (pinfunction "6_6") (pintype "passive"))
    )
    (net (code "281") (name "unconnected-(J32-Pad7)") (class "Default")
      (node (ref "J32") (pin "7") (pinfunction "7_7") (pintype "passive"))
    )
    (net (code "282") (name "unconnected-(J32-Pad8)") (class "Default")
      (node (ref "J32") (pin "8") (pinfunction "8_8") (pintype "passive"))
    )
    (net (code "283") (name "unconnected-(J33-Pad1)") (class "Default")
      (node (ref "J33") (pin "1") (pinfunction "1_1") (pintype "passive"))
    )
    (net (code "284") (name "unconnected-(J33-Pad2)") (class "Default")
      (node (ref "J33") (pin "2") (pinfunction "2_2") (pintype "passive"))
    )
    (net (code "285") (name "unconnected-(J33-Pad3)") (class "Default")
      (node (ref "J33") (pin "3") (pinfunction "3_3") (pintype "passive"))
    )
    (net (code "286") (name "unconnected-(J33-Pad4)") (class "Default")
      (node (ref "J33") (pin "4") (pinfunction "4_4") (pintype "passive"))
    )
    (net (code "287") (name "unconnected-(J33-Pad5)") (class "Default")
      (node (ref "J33") (pin "5") (pinfunction "5_5") (pintype "passive"))
    )
    (net (code "288") (name "unconnected-(J33-Pad6)") (class "Default")
      (node (ref "J33") (pin "6") (pinfunction "6_6") (pintype "passive"))
    )
    (net (code "289") (name "unconnected-(J33-Pad7)") (class "Default")
      (node (ref "J33") (pin "7") (pinfunction "7_7") (pintype "passive"))
    )
    (net (code "290") (name "unconnected-(J33-Pad8)") (class "Default")
      (node (ref "J33") (pin "8") (pinfunction "8_8") (pintype "passive"))
    )
    (net (code "291") (name "unconnected-(J34-Pad1)") (class "Default")
      (node (ref "J34") (pin "1") (pinfunction "1_1") (pintype "passive"))
    )
    (net (code "292") (name "unconnected-(J34-Pad2)") (class "Default")
      (node (ref "J34") (pin "2") (pinfunction "2_2") (pintype "passive"))
    )
    (net (code "293") (name "unconnected-(J34-Pad3)") (class "Default")
      (node (ref "J34") (pin "3") (pinfunction "3_3") (pintype "passive"))
    )
    (net (code "294") (name "unconnected-(J34-Pad4)") (class "Default")
      (node (ref "J34") (pin "4") (pinfunction "4_4") (pintype "passive"))
    )
    (net (code "295") (name "unconnected-(J34-Pad5)") (class "Default")
      (node (ref "J34") (pin "5") (pinfunction "5_5") (pintype "passive"))
    )
    (net (code "296") (name "unconnected-(J34-Pad6)") (class "Default")
      (node (ref "J34") (pin "6") (pinfunction "6_6") (pintype "passive"))
    )
    (net (code "297") (name "unconnected-(J34-Pad7)") (class "Default")
      (node (ref "J34") (pin "7") (pinfunction "7_7") (pintype "passive"))
    )
    (net (code "298") (name "unconnected-(J34-Pad8)") (class "Default")
      (node (ref "J34") (pin "8") (pinfunction "8_8") (pintype "passive"))
    )
    (net (code "299") (name "unconnected-(S1-S-Pad3)") (class "Default")
      (node (ref "S1") (pin "3") (pinfunction "S_3") (pintype "passive"))
    )
  )
)
